# YYB-Sheet1.net
KiCad netlist of a schematic drawn in Altium Designer
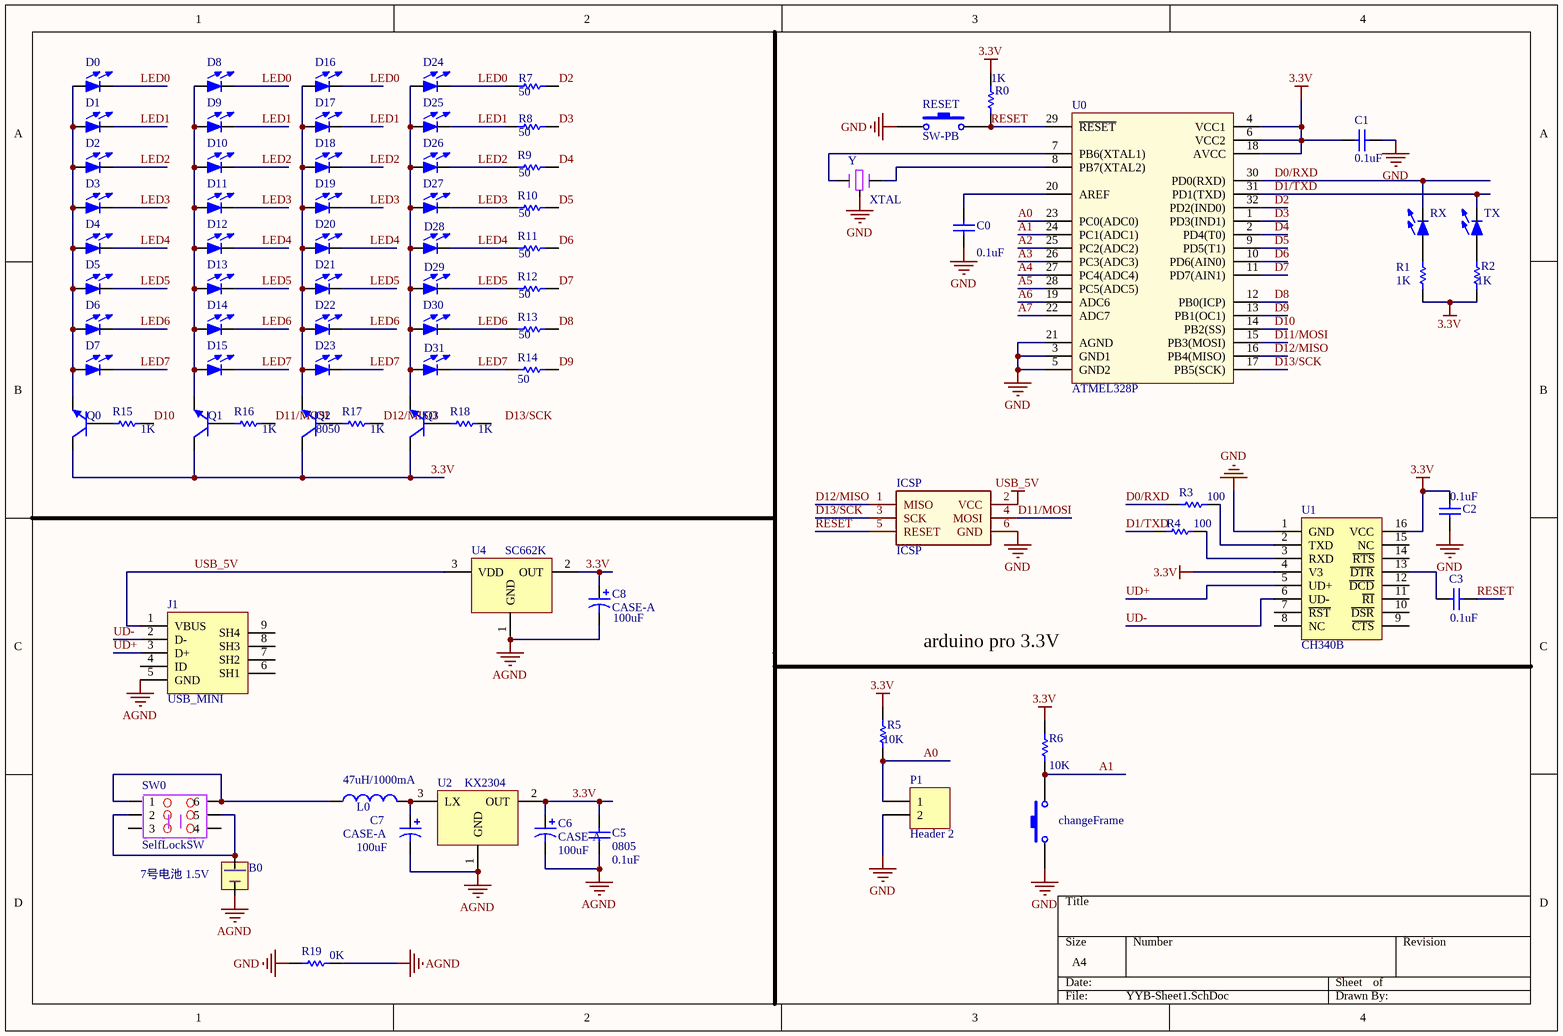
[diagram p0: YYB-Sheet1.SchDoc]

(export (version "E")
  (design (tool "Eeschema 10.0.6"))
  (components
    (comp (ref "B0") (value "7号电池 1.5V") (footprint "BAT") (libsource (lib "aistlab") (part "Battery")))
    (comp (ref "C0")
      (value "0.1uF")
      (footprint "6-0805_N")
      (description "Capacitor")
      (fields (field (name "PUBLISHER") "Altium Limited"))
      (libsource (lib "Miscellaneous Devices") (part "Cap"))
    )
    (comp (ref "C1")
      (value "0.1uF")
      (footprint "6-0805_N")
      (description "Capacitor")
      (fields (field (name "Comment") "Cap") (field (name "PUBLISHER") "Altium Limited"))
      (libsource (lib "Miscellaneous Devices") (part "Cap"))
    )
    (comp (ref "C2")
      (value "0.1uF")
      (footprint "6-0805_N")
      (description "Capacitor")
      (fields (field (name "Comment") "Cap") (field (name "PUBLISHER") "Altium Limited"))
      (libsource (lib "Miscellaneous Devices") (part "Cap"))
    )
    (comp (ref "C3")
      (value "0.1uF")
      (footprint "6-0805_N")
      (description "Capacitor")
      (fields (field (name "Comment") "Cap") (field (name "PUBLISHER") "Altium Limited"))
      (libsource (lib "Miscellaneous Devices") (part "Cap"))
    )
    (comp (ref "C5")
      (value "0805")
      (footprint "6-0805_N")
      (description "Capacitor")
      (fields (field (name "ALTIUM_VALUE") "0.1uF") (field (name "PUBLISHER") "Altium Limited"))
      (libsource (lib "Miscellaneous Devices") (part "Cap"))
    )
    (comp (ref "C6")
      (value "CASE-A")
      (footprint "CASE-A_3216")
      (description "Polarized Capacitor (Radial)")
      (fields (field (name "ALTIUM_VALUE") "100uF") (field (name "PUBLISHER") "Altium Limited"))
      (libsource (lib "Miscellaneous Devices") (part "Cap Pol1"))
    )
    (comp (ref "C7")
      (value "CASE-A")
      (footprint "CASE-A_3216")
      (description "Polarized Capacitor (Radial)")
      (fields (field (name "ALTIUM_VALUE") "100uF") (field (name "PUBLISHER") "Altium Limited"))
      (libsource (lib "Miscellaneous Devices") (part "Cap Pol1"))
    )
    (comp (ref "C8")
      (value "CASE-A")
      (footprint "CASE-A_3216")
      (description "Polarized Capacitor (Radial)")
      (fields (field (name "ALTIUM_VALUE") "100uF") (field (name "PUBLISHER") "Altium Limited"))
      (libsource (lib "Miscellaneous Devices") (part "Cap Pol1"))
    )
    (comp (ref "changeFrame")
      (value "SW-PB")
      (footprint "KEY_SODFL_2-Leads")
      (description "Switch")
      (fields (field (name "PUBLISHER") "Altium Limited"))
      (libsource (lib "Miscellaneous Devices") (part "SW-PB"))
    )
    (comp (ref "D0") (value "~") (footprint "LED_3528") (libsource (lib "aistlab") (part "LED")))
    (comp (ref "D1") (value "~") (footprint "LED_3528") (libsource (lib "aistlab") (part "LED")))
    (comp (ref "D2") (value "~") (footprint "LED_3528") (libsource (lib "aistlab") (part "LED")))
    (comp (ref "D3") (value "~") (footprint "LED_3528") (libsource (lib "aistlab") (part "LED")))
    (comp (ref "D4") (value "~") (footprint "LED_3528") (libsource (lib "aistlab") (part "LED")))
    (comp (ref "D5") (value "~") (footprint "LED_3528") (libsource (lib "aistlab") (part "LED")))
    (comp (ref "D6") (value "~") (footprint "LED_3528") (libsource (lib "aistlab") (part "LED")))
    (comp (ref "D7") (value "~") (footprint "LED_3528") (libsource (lib "aistlab") (part "LED")))
    (comp (ref "D8") (value "~") (footprint "LED_3528") (libsource (lib "aistlab") (part "LED")))
    (comp (ref "D9") (value "~") (footprint "LED_3528") (libsource (lib "aistlab") (part "LED")))
    (comp (ref "D10") (value "~") (footprint "LED_3528") (libsource (lib "aistlab") (part "LED")))
    (comp (ref "D11") (value "~") (footprint "LED_3528") (libsource (lib "aistlab") (part "LED")))
    (comp (ref "D12") (value "~") (footprint "LED_3528") (libsource (lib "aistlab") (part "LED")))
    (comp (ref "D13") (value "~") (footprint "LED_3528") (libsource (lib "aistlab") (part "LED")))
    (comp (ref "D14") (value "~") (footprint "LED_3528") (libsource (lib "aistlab") (part "LED")))
    (comp (ref "D15") (value "~") (footprint "LED_3528") (libsource (lib "aistlab") (part "LED")))
    (comp (ref "D16") (value "~") (footprint "LED_3528") (libsource (lib "aistlab") (part "LED")))
    (comp (ref "D17") (value "~") (footprint "LED_3528") (libsource (lib "aistlab") (part "LED")))
    (comp (ref "D18") (value "~") (footprint "LED_3528") (libsource (lib "aistlab") (part "LED")))
    (comp (ref "D19") (value "~") (footprint "LED_3528") (libsource (lib "aistlab") (part "LED")))
    (comp (ref "D20") (value "~") (footprint "LED_3528") (libsource (lib "aistlab") (part "LED")))
    (comp (ref "D21") (value "~") (footprint "LED_3528") (libsource (lib "aistlab") (part "LED")))
    (comp (ref "D22") (value "~") (footprint "LED_3528") (libsource (lib "aistlab") (part "LED")))
    (comp (ref "D23") (value "~") (footprint "LED_3528") (libsource (lib "aistlab") (part "LED")))
    (comp (ref "D24") (value "~") (footprint "LED_3528") (libsource (lib "aistlab") (part "LED")))
    (comp (ref "D25") (value "~") (footprint "LED_3528") (libsource (lib "aistlab") (part "LED")))
    (comp (ref "D26") (value "~") (footprint "LED_3528") (libsource (lib "aistlab") (part "LED")))
    (comp (ref "D27") (value "~") (footprint "LED_3528") (libsource (lib "aistlab") (part "LED")))
    (comp (ref "D28") (value "~") (footprint "LED_3528") (libsource (lib "aistlab") (part "LED")))
    (comp (ref "D29") (value "~") (footprint "LED_3528") (libsource (lib "aistlab") (part "LED")))
    (comp (ref "D30") (value "~") (footprint "LED_3528") (libsource (lib "aistlab") (part "LED")))
    (comp (ref "D31") (value "~") (footprint "LED_3528") (libsource (lib "aistlab") (part "LED")))
    (comp (ref "ICSP") (value "ICSP") (footprint "HDR2X3") (libsource (lib "aistlab") (part "ICSP")))
    (comp (ref "J1")
      (value "USB_MINI")
      (footprint "MICRO_USB")
      (libsource (lib "YYB-Schlib1") (part "USB_MINI"))
    )
    (comp (ref "L0")
      (value "47uH/1000mA")
      (footprint "0402-A")
      (description "Inductor")
      (fields (field (name "PUBLISHER") "Altium Limited"))
      (libsource (lib "Miscellaneous Devices") (part "Inductor"))
    )
    (comp (ref "P1")
      (value "Header 2")
      (footprint "HDR1X2")
      (description "Header, 2-Pin")
      (fields (field (name "PUBLISHER") "Altium Limited"))
      (libsource (lib "Miscellaneous Connectors") (part "Header 2"))
    )
    (comp (ref "Q0")
      (value "transistor")
      (footprint "SOT-23")
      (libsource (lib "aistlab") (part "transistor"))
    )
    (comp (ref "Q1")
      (value "transistor")
      (footprint "SOT-23")
      (libsource (lib "aistlab") (part "transistor"))
    )
    (comp (ref "Q2") (value "8050") (footprint "SOT-23") (libsource (lib "aistlab") (part "transistor")))
    (comp (ref "Q3")
      (value "transistor")
      (footprint "SOT-23")
      (libsource (lib "aistlab") (part "transistor"))
    )
    (comp (ref "R0")
      (value "1K")
      (footprint "6-0805_N")
      (description "Resistor")
      (fields (field (name "PUBLISHER") "Altium Limited"))
      (libsource (lib "Miscellaneous Devices") (part "Res1"))
    )
    (comp (ref "R1")
      (value "1K")
      (footprint "6-0805_N")
      (description "Resistor")
      (fields (field (name "Comment") "Res1") (field (name "PUBLISHER") "Altium Limited"))
      (libsource (lib "Miscellaneous Devices") (part "Res1"))
    )
    (comp (ref "R2")
      (value "1K")
      (footprint "6-0805_N")
      (description "Resistor")
      (fields (field (name "Comment") "Res1") (field (name "PUBLISHER") "Altium Limited"))
      (libsource (lib "Miscellaneous Devices") (part "Res1"))
    )
    (comp (ref "R3")
      (value "100")
      (footprint "6-0805_N")
      (description "Resistor")
      (fields (field (name "Comment") "Res1") (field (name "PUBLISHER") "Altium Limited"))
      (libsource (lib "Miscellaneous Devices") (part "Res1"))
    )
    (comp (ref "R4")
      (value "100")
      (footprint "6-0805_N")
      (description "Resistor")
      (fields (field (name "Comment") "Res1") (field (name "PUBLISHER") "Altium Limited"))
      (libsource (lib "Miscellaneous Devices") (part "Res1"))
    )
    (comp (ref "R5")
      (value "10K")
      (footprint "6-0805_N")
      (description "Resistor")
      (fields (field (name "Comment") "Res1") (field (name "PUBLISHER") "Altium Limited"))
      (libsource (lib "Miscellaneous Devices") (part "Res1"))
    )
    (comp (ref "R6")
      (value "10K")
      (footprint "6-0805_N")
      (description "Resistor")
      (fields (field (name "Comment") "Res1") (field (name "PUBLISHER") "Altium Limited"))
      (libsource (lib "Miscellaneous Devices") (part "Res1"))
    )
    (comp (ref "R7")
      (value "50")
      (footprint "6-0805_N")
      (description "Resistor")
      (fields (field (name "Comment") "Res1") (field (name "PUBLISHER") "Altium Limited"))
      (libsource (lib "Miscellaneous Devices") (part "Res1"))
    )
    (comp (ref "R8")
      (value "50")
      (footprint "6-0805_N")
      (description "Resistor")
      (fields (field (name "Comment") "Res1") (field (name "PUBLISHER") "Altium Limited"))
      (libsource (lib "Miscellaneous Devices") (part "Res1"))
    )
    (comp (ref "R9")
      (value "50")
      (footprint "6-0805_N")
      (description "Resistor")
      (fields (field (name "Comment") "Res1") (field (name "PUBLISHER") "Altium Limited"))
      (libsource (lib "Miscellaneous Devices") (part "Res1"))
    )
    (comp (ref "R10")
      (value "50")
      (footprint "6-0805_N")
      (description "Resistor")
      (fields (field (name "Comment") "Res1") (field (name "PUBLISHER") "Altium Limited"))
      (libsource (lib "Miscellaneous Devices") (part "Res1"))
    )
    (comp (ref "R11")
      (value "50")
      (footprint "6-0805_N")
      (description "Resistor")
      (fields (field (name "Comment") "Res1") (field (name "PUBLISHER") "Altium Limited"))
      (libsource (lib "Miscellaneous Devices") (part "Res1"))
    )
    (comp (ref "R12")
      (value "50")
      (footprint "6-0805_N")
      (description "Resistor")
      (fields (field (name "Comment") "Res1") (field (name "PUBLISHER") "Altium Limited"))
      (libsource (lib "Miscellaneous Devices") (part "Res1"))
    )
    (comp (ref "R13")
      (value "50")
      (footprint "6-0805_N")
      (description "Resistor")
      (fields (field (name "Comment") "Res1") (field (name "PUBLISHER") "Altium Limited"))
      (libsource (lib "Miscellaneous Devices") (part "Res1"))
    )
    (comp (ref "R14")
      (value "50")
      (description "Resistor")
      (fields (field (name "Comment") "Res1") (field (name "PUBLISHER") "Altium Limited"))
      (libsource (lib "Miscellaneous Devices") (part "Res1"))
    )
    (comp (ref "R15")
      (value "1K")
      (footprint "6-0805_N")
      (description "Resistor")
      (fields (field (name "Comment") "Res1") (field (name "PUBLISHER") "Altium Limited"))
      (libsource (lib "Miscellaneous Devices") (part "Res1"))
    )
    (comp (ref "R16")
      (value "1K")
      (footprint "6-0805_N")
      (description "Resistor")
      (fields (field (name "Comment") "Res1") (field (name "PUBLISHER") "Altium Limited"))
      (libsource (lib "Miscellaneous Devices") (part "Res1"))
    )
    (comp (ref "R17")
      (value "1K")
      (footprint "6-0805_N")
      (description "Resistor")
      (fields (field (name "Comment") "Res1") (field (name "PUBLISHER") "Altium Limited"))
      (libsource (lib "Miscellaneous Devices") (part "Res1"))
    )
    (comp (ref "R18")
      (value "1K")
      (footprint "6-0805_N")
      (description "Resistor")
      (fields (field (name "Comment") "Res1") (field (name "PUBLISHER") "Altium Limited"))
      (libsource (lib "Miscellaneous Devices") (part "Res1"))
    )
    (comp (ref "R19")
      (value "0K")
      (footprint "6-0805_N")
      (description "Resistor")
      (fields (field (name "Comment") "Res1") (field (name "PUBLISHER") "Altium Limited"))
      (libsource (lib "Miscellaneous Devices") (part "Res1"))
    )
    (comp (ref "RESET")
      (value "SW-PB")
      (footprint "KEY_SODFL_2-Leads")
      (description "Switch")
      (fields (field (name "PUBLISHER") "Altium Limited"))
      (libsource (lib "Miscellaneous Devices") (part "SW-PB"))
    )
    (comp (ref "RX") (value "~") (footprint "LED_0805") (libsource (lib "aistlab") (part "LED")))
    (comp (ref "SW0")
      (value "SelfLockSW")
      (footprint "KEY_ZS_8*8")
      (description "自锁开关")
      (libsource (lib "aistlab") (part "SelfLockSwitch"))
    )
    (comp (ref "TX") (value "~") (footprint "LED_0805") (libsource (lib "aistlab") (part "LED")))
    (comp (ref "U0")
      (value "ATMEL328P")
      (footprint "TQFP 32")
      (libsource (lib "aistlab") (part "ATMEL-328P"))
    )
    (comp (ref "U1")
      (value "CH340B")
      (footprint "SOP16")
      (description "usb to uart")
      (libsource (lib "aistlab") (part "CH340B"))
    )
    (comp (ref "U2") (value "KX2304") (footprint "SOT89N") (libsource (lib "aistlab") (part "KX2304")))
    (comp (ref "U4")
      (value "SC662K")
      (footprint "SOT-23")
      (description "3.3V 稳压芯片")
      (libsource (lib "aistlab") (part "SC662k-3.3V"))
    )
    (comp (ref "Y") (value "XTAL") (footprint "XTAL") (libsource (lib "aistlab") (part "XTAL")))
  )
  (nets
    (net (code "1") (name "/A0") (class "Default")
      (node (ref "P1") (pin "1") (pinfunction "1_1") (pintype "passive"))
      (node (ref "R5") (pin "1") (pinfunction "1_1") (pintype "passive"))
      (node (ref "U0") (pin "23") (pinfunction "PC0(ADC0)_23") (pintype "open_collector"))
    )
    (net (code "2") (name "/A1") (class "Default")
      (node (ref "R6") (pin "1") (pinfunction "1_1") (pintype "passive"))
      (node (ref "U0") (pin "24") (pinfunction "PC1(ADC1)_24") (pintype "open_collector"))
      (node (ref "changeFrame") (pin "2") (pinfunction "2_2") (pintype "passive"))
    )
    (net (code "3") (name "/A2") (class "Default")
      (node (ref "U0") (pin "25") (pinfunction "PC2(ADC2)_25") (pintype "open_collector"))
    )
    (net (code "4") (name "/A3") (class "Default")
      (node (ref "U0") (pin "26") (pinfunction "PC3(ADC3)_26") (pintype "open_collector"))
    )
    (net (code "5") (name "/A4") (class "Default")
      (node (ref "U0") (pin "27") (pinfunction "PC4(ADC4)_27") (pintype "open_collector"))
    )
    (net (code "6") (name "/A5") (class "Default")
      (node (ref "U0") (pin "28") (pinfunction "PC5(ADC5)_28") (pintype "open_collector"))
    )
    (net (code "7") (name "/A6") (class "Default")
      (node (ref "U0") (pin "19") (pinfunction "ADC6_19") (pintype "open_collector"))
    )
    (net (code "8") (name "/A7") (class "Default")
      (node (ref "U0") (pin "22") (pinfunction "ADC7_22") (pintype "open_collector"))
    )
    (net (code "9") (name "/D0{slash}RXD") (class "Default")
      (node (ref "R3") (pin "1") (pinfunction "1_1") (pintype "passive"))
      (node (ref "RX") (pin "2") (pinfunction "2_2") (pintype "passive"))
      (node (ref "U0") (pin "30") (pinfunction "PD0(RXD)_30") (pintype "open_collector"))
    )
    (net (code "10") (name "/D1{slash}TXD") (class "Default")
      (node (ref "R4") (pin "1") (pinfunction "1_1") (pintype "passive"))
      (node (ref "TX") (pin "2") (pinfunction "2_2") (pintype "passive"))
      (node (ref "U0") (pin "31") (pinfunction "PD1(TXD)_31") (pintype "open_collector"))
    )
    (net (code "11") (name "/D2") (class "Default")
      (node (ref "R7") (pin "2") (pinfunction "2_2") (pintype "passive"))
      (node (ref "U0") (pin "32") (pinfunction "PD2(IND0)_32") (pintype "open_collector"))
    )
    (net (code "12") (name "/D3") (class "Default")
      (node (ref "R8") (pin "2") (pinfunction "2_2") (pintype "passive"))
      (node (ref "U0") (pin "1") (pinfunction "PD3(IND1)_1") (pintype "open_collector"))
    )
    (net (code "13") (name "/D4") (class "Default")
      (node (ref "R9") (pin "2") (pinfunction "2_2") (pintype "passive"))
      (node (ref "U0") (pin "2") (pinfunction "PD4(T0)_2") (pintype "open_collector"))
    )
    (net (code "14") (name "/D5") (class "Default")
      (node (ref "R10") (pin "2") (pinfunction "2_2") (pintype "passive"))
      (node (ref "U0") (pin "9") (pinfunction "PD5(T1)_9") (pintype "open_collector"))
    )
    (net (code "15") (name "/D6") (class "Default")
      (node (ref "R11") (pin "2") (pinfunction "2_2") (pintype "passive"))
      (node (ref "U0") (pin "10") (pinfunction "PD6(AIN0)_10") (pintype "open_collector"))
    )
    (net (code "16") (name "/D7") (class "Default")
      (node (ref "R12") (pin "2") (pinfunction "2_2") (pintype "passive"))
      (node (ref "U0") (pin "11") (pinfunction "PD7(AIN1)_11") (pintype "open_collector"))
    )
    (net (code "17") (name "/D8") (class "Default")
      (node (ref "R13") (pin "2") (pinfunction "2_2") (pintype "passive"))
      (node (ref "U0") (pin "12") (pinfunction "PB0(ICP)_12") (pintype "open_collector"))
    )
    (net (code "18") (name "/D9") (class "Default")
      (node (ref "R14") (pin "2") (pinfunction "2_2") (pintype "passive"))
      (node (ref "U0") (pin "13") (pinfunction "PB1(OC1)_13") (pintype "open_collector"))
    )
    (net (code "19") (name "/D10") (class "Default")
      (node (ref "R15") (pin "2") (pinfunction "2_2") (pintype "passive"))
      (node (ref "U0") (pin "14") (pinfunction "PB2(SS)_14") (pintype "open_collector"))
    )
    (net (code "20") (name "/D11{slash}MOSI") (class "Default")
      (node (ref "ICSP") (pin "4") (pinfunction "MOSI_4") (pintype "open_collector"))
      (node (ref "R16") (pin "2") (pinfunction "2_2") (pintype "passive"))
      (node (ref "U0") (pin "15") (pinfunction "PB3(MOSI)_15") (pintype "open_collector"))
    )
    (net (code "21") (name "/D12{slash}MISO") (class "Default")
      (node (ref "ICSP") (pin "1") (pinfunction "MISO_1") (pintype "open_collector"))
      (node (ref "R17") (pin "2") (pinfunction "2_2") (pintype "passive"))
      (node (ref "U0") (pin "16") (pinfunction "PB4(MISO)_16") (pintype "open_collector"))
    )
    (net (code "22") (name "/D13{slash}SCK") (class "Default")
      (node (ref "ICSP") (pin "3") (pinfunction "SCK_3") (pintype "open_collector"))
      (node (ref "U0") (pin "17") (pinfunction "PB5(SCK)_17") (pintype "open_collector"))
    )
    (net (code "23") (name "/LED0") (class "Default")
      (node (ref "D0") (pin "2") (pinfunction "2_2") (pintype "passive"))
      (node (ref "D16") (pin "2") (pinfunction "2_2") (pintype "passive"))
      (node (ref "D24") (pin "2") (pinfunction "2_2") (pintype "passive"))
      (node (ref "D8") (pin "2") (pinfunction "2_2") (pintype "passive"))
      (node (ref "R7") (pin "1") (pinfunction "1_1") (pintype "passive"))
    )
    (net (code "24") (name "/LED1") (class "Default")
      (node (ref "D1") (pin "2") (pinfunction "2_2") (pintype "passive"))
      (node (ref "D17") (pin "2") (pinfunction "2_2") (pintype "passive"))
      (node (ref "D25") (pin "2") (pinfunction "2_2") (pintype "passive"))
      (node (ref "D9") (pin "2") (pinfunction "2_2") (pintype "passive"))
      (node (ref "R8") (pin "1") (pinfunction "1_1") (pintype "passive"))
    )
    (net (code "25") (name "/LED2") (class "Default")
      (node (ref "D10") (pin "2") (pinfunction "2_2") (pintype "passive"))
      (node (ref "D18") (pin "2") (pinfunction "2_2") (pintype "passive"))
      (node (ref "D2") (pin "2") (pinfunction "2_2") (pintype "passive"))
      (node (ref "D26") (pin "2") (pinfunction "2_2") (pintype "passive"))
      (node (ref "R9") (pin "1") (pinfunction "1_1") (pintype "passive"))
    )
    (net (code "26") (name "/LED3") (class "Default")
      (node (ref "D11") (pin "2") (pinfunction "2_2") (pintype "passive"))
      (node (ref "D19") (pin "2") (pinfunction "2_2") (pintype "passive"))
      (node (ref "D27") (pin "2") (pinfunction "2_2") (pintype "passive"))
      (node (ref "D3") (pin "2") (pinfunction "2_2") (pintype "passive"))
      (node (ref "R10") (pin "1") (pinfunction "1_1") (pintype "passive"))
    )
    (net (code "27") (name "/LED4") (class "Default")
      (node (ref "D12") (pin "2") (pinfunction "2_2") (pintype "passive"))
      (node (ref "D20") (pin "2") (pinfunction "2_2") (pintype "passive"))
      (node (ref "D28") (pin "2") (pinfunction "2_2") (pintype "passive"))
      (node (ref "D4") (pin "2") (pinfunction "2_2") (pintype "passive"))
      (node (ref "R11") (pin "1") (pinfunction "1_1") (pintype "passive"))
    )
    (net (code "28") (name "/LED5") (class "Default")
      (node (ref "D13") (pin "2") (pinfunction "2_2") (pintype "passive"))
      (node (ref "D21") (pin "2") (pinfunction "2_2") (pintype "passive"))
      (node (ref "D29") (pin "2") (pinfunction "2_2") (pintype "passive"))
      (node (ref "D5") (pin "2") (pinfunction "2_2") (pintype "passive"))
      (node (ref "R12") (pin "1") (pinfunction "1_1") (pintype "passive"))
    )
    (net (code "29") (name "/LED6") (class "Default")
      (node (ref "D14") (pin "2") (pinfunction "2_2") (pintype "passive"))
      (node (ref "D22") (pin "2") (pinfunction "2_2") (pintype "passive"))
      (node (ref "D30") (pin "2") (pinfunction "2_2") (pintype "passive"))
      (node (ref "D6") (pin "2") (pinfunction "2_2") (pintype "passive"))
      (node (ref "R13") (pin "1") (pinfunction "1_1") (pintype "passive"))
    )
    (net (code "30") (name "/LED7") (class "Default")
      (node (ref "D15") (pin "2") (pinfunction "2_2") (pintype "passive"))
      (node (ref "D23") (pin "2") (pinfunction "2_2") (pintype "passive"))
      (node (ref "D31") (pin "2") (pinfunction "2_2") (pintype "passive"))
      (node (ref "D7") (pin "2") (pinfunction "2_2") (pintype "passive"))
      (node (ref "R14") (pin "1") (pinfunction "1_1") (pintype "passive"))
    )
    (net (code "31") (name "/RESET") (class "Default")
      (node (ref "C3") (pin "2") (pinfunction "2_2") (pintype "passive"))
      (node (ref "ICSP") (pin "5") (pinfunction "RESET_5") (pintype "open_collector"))
      (node (ref "R0") (pin "2") (pinfunction "2_2") (pintype "passive"))
      (node (ref "RESET") (pin "2") (pinfunction "2_2") (pintype "passive"))
      (node (ref "U0") (pin "29") (pinfunction "~{RESET}_29") (pintype "open_collector"))
    )
    (net (code "32") (name "/UD+") (class "Default")
      (node (ref "J1") (pin "3") (pinfunction "D+_3") (pintype "passive"))
      (node (ref "U1") (pin "5") (pinfunction "UD+_5") (pintype "open_collector"))
    )
    (net (code "33") (name "/UD-") (class "Default")
      (node (ref "J1") (pin "2") (pinfunction "D-_2") (pintype "passive"))
      (node (ref "U1") (pin "6") (pinfunction "UD-_6") (pintype "open_collector"))
    )
    (net (code "34") (name "3.3V") (class "Default")
      (node (ref "C1") (pin "2") (pinfunction "2_2") (pintype "passive"))
      (node (ref "C2") (pin "2") (pinfunction "2_2") (pintype "passive"))
      (node (ref "C5") (pin "2") (pinfunction "2_2") (pintype "passive"))
      (node (ref "C6") (pin "1") (pinfunction "1_1") (pintype "passive"))
      (node (ref "C8") (pin "1") (pinfunction "1_1") (pintype "passive"))
      (node (ref "Q0") (pin "3") (pinfunction "C_3") (pintype "passive"))
      (node (ref "Q1") (pin "3") (pinfunction "C_3") (pintype "passive"))
      (node (ref "Q2") (pin "3") (pinfunction "C_3") (pintype "passive"))
      (node (ref "Q3") (pin "3") (pinfunction "C_3") (pintype "passive"))
      (node (ref "R0") (pin "1") (pinfunction "1_1") (pintype "passive"))
      (node (ref "R1") (pin "1") (pinfunction "1_1") (pintype "passive"))
      (node (ref "R2") (pin "1") (pinfunction "1_1") (pintype "passive"))
      (node (ref "R5") (pin "2") (pinfunction "2_2") (pintype "passive"))
      (node (ref "R6") (pin "2") (pinfunction "2_2") (pintype "passive"))
      (node (ref "U0") (pin "18") (pinfunction "AVCC_18") (pintype "power_in"))
      (node (ref "U0") (pin "4") (pinfunction "VCC1_4") (pintype "power_in"))
      (node (ref "U0") (pin "6") (pinfunction "VCC2_6") (pintype "power_in"))
      (node (ref "U1") (pin "16") (pinfunction "VCC_16") (pintype "power_in"))
      (node (ref "U1") (pin "4") (pinfunction "V3_4") (pintype "power_in"))
      (node (ref "U2") (pin "2") (pinfunction "OUT_2") (pintype "passive"))
      (node (ref "U4") (pin "2") (pinfunction "OUT_2") (pintype "passive"))
    )
    (net (code "35") (name "AGND") (class "Default")
      (node (ref "B0") (pin "2") (pinfunction "2_2") (pintype "passive"))
      (node (ref "C5") (pin "1") (pinfunction "1_1") (pintype "passive"))
      (node (ref "C6") (pin "2") (pinfunction "2_2") (pintype "passive"))
      (node (ref "C7") (pin "2") (pinfunction "2_2") (pintype "passive"))
      (node (ref "C8") (pin "2") (pinfunction "2_2") (pintype "passive"))
      (node (ref "J1") (pin "5") (pinfunction "GND_5") (pintype "passive"))
      (node (ref "R19") (pin "2") (pinfunction "2_2") (pintype "passive"))
      (node (ref "U2") (pin "1") (pinfunction "GND_1") (pintype "passive"))
      (node (ref "U4") (pin "1") (pinfunction "GND_1") (pintype "open_collector"))
    )
    (net (code "36") (name "GND") (class "Default")
      (node (ref "C0") (pin "1") (pinfunction "1_1") (pintype "passive"))
      (node (ref "C1") (pin "1") (pinfunction "1_1") (pintype "passive"))
      (node (ref "C2") (pin "1") (pinfunction "1_1") (pintype "passive"))
      (node (ref "ICSP") (pin "6") (pinfunction "GND_6") (pintype "open_collector"))
      (node (ref "P1") (pin "2") (pinfunction "2_2") (pintype "passive"))
      (node (ref "R19") (pin "1") (pinfunction "1_1") (pintype "passive"))
      (node (ref "RESET") (pin "1") (pinfunction "1_1") (pintype "passive"))
      (node (ref "U0") (pin "21") (pinfunction "AGND_21") (pintype "open_collector"))
      (node (ref "U0") (pin "3") (pinfunction "GND1_3") (pintype "open_collector"))
      (node (ref "U0") (pin "5") (pinfunction "GND2_5") (pintype "open_collector"))
      (node (ref "U1") (pin "1") (pinfunction "GND_1") (pintype "open_collector"))
      (node (ref "Y") (pin "2") (pinfunction "2_2") (pintype "passive"))
      (node (ref "changeFrame") (pin "1") (pinfunction "1_1") (pintype "passive"))
    )
    (net (code "37") (name "Net-(B0-+)") (class "Default")
      (node (ref "B0") (pin "1") (pinfunction "+_1") (pintype "passive"))
      (node (ref "SW0") (pin "2") (pinfunction "2_2") (pintype "passive"))
      (node (ref "SW0") (pin "5") (pinfunction "5_5") (pintype "passive"))
    )
    (net (code "38") (name "Net-(L0-Pad1)") (class "Default")
      (node (ref "L0") (pin "1") (pinfunction "1_1") (pintype "passive"))
      (node (ref "SW0") (pin "1") (pinfunction "1_1") (pintype "passive"))
      (node (ref "SW0") (pin "6") (pinfunction "6_6") (pintype "passive"))
    )
    (net (code "39") (name "Net-(Q0-B)") (class "Default")
      (node (ref "Q0") (pin "1") (pinfunction "B_1") (pintype "passive"))
      (node (ref "R15") (pin "1") (pinfunction "1_1") (pintype "passive"))
    )
    (net (code "40") (name "Net-(Q0-E)") (class "Default")
      (node (ref "D0") (pin "1") (pinfunction "1_1") (pintype "passive"))
      (node (ref "D1") (pin "1") (pinfunction "1_1") (pintype "passive"))
      (node (ref "D2") (pin "1") (pinfunction "1_1") (pintype "passive"))
      (node (ref "D3") (pin "1") (pinfunction "1_1") (pintype "passive"))
      (node (ref "D4") (pin "1") (pinfunction "1_1") (pintype "passive"))
      (node (ref "D5") (pin "1") (pinfunction "1_1") (pintype "passive"))
      (node (ref "D6") (pin "1") (pinfunction "1_1") (pintype "passive"))
      (node (ref "D7") (pin "1") (pinfunction "1_1") (pintype "passive"))
      (node (ref "Q0") (pin "2") (pinfunction "E_2") (pintype "passive"))
    )
    (net (code "41") (name "Net-(Q1-B)") (class "Default")
      (node (ref "Q1") (pin "1") (pinfunction "B_1") (pintype "passive"))
      (node (ref "R16") (pin "1") (pinfunction "1_1") (pintype "passive"))
    )
    (net (code "42") (name "Net-(Q1-E)") (class "Default")
      (node (ref "D10") (pin "1") (pinfunction "1_1") (pintype "passive"))
      (node (ref "D11") (pin "1") (pinfunction "1_1") (pintype "passive"))
      (node (ref "D12") (pin "1") (pinfunction "1_1") (pintype "passive"))
      (node (ref "D13") (pin "1") (pinfunction "1_1") (pintype "passive"))
      (node (ref "D14") (pin "1") (pinfunction "1_1") (pintype "passive"))
      (node (ref "D15") (pin "1") (pinfunction "1_1") (pintype "passive"))
      (node (ref "D8") (pin "1") (pinfunction "1_1") (pintype "passive"))
      (node (ref "D9") (pin "1") (pinfunction "1_1") (pintype "passive"))
      (node (ref "Q1") (pin "2") (pinfunction "E_2") (pintype "passive"))
    )
    (net (code "43") (name "Net-(Q2-B)") (class "Default")
      (node (ref "Q2") (pin "1") (pinfunction "B_1") (pintype "passive"))
      (node (ref "R17") (pin "1") (pinfunction "1_1") (pintype "passive"))
    )
    (net (code "44") (name "Net-(Q2-E)") (class "Default")
      (node (ref "D16") (pin "1") (pinfunction "1_1") (pintype "passive"))
      (node (ref "D17") (pin "1") (pinfunction "1_1") (pintype "passive"))
      (node (ref "D18") (pin "1") (pinfunction "1_1") (pintype "passive"))
      (node (ref "D19") (pin "1") (pinfunction "1_1") (pintype "passive"))
      (node (ref "D20") (pin "1") (pinfunction "1_1") (pintype "passive"))
      (node (ref "D21") (pin "1") (pinfunction "1_1") (pintype "passive"))
      (node (ref "D22") (pin "1") (pinfunction "1_1") (pintype "passive"))
      (node (ref "D23") (pin "1") (pinfunction "1_1") (pintype "passive"))
      (node (ref "Q2") (pin "2") (pinfunction "E_2") (pintype "passive"))
    )
    (net (code "45") (name "Net-(Q3-B)") (class "Default")
      (node (ref "Q3") (pin "1") (pinfunction "B_1") (pintype "passive"))
      (node (ref "R18") (pin "1") (pinfunction "1_1") (pintype "passive"))
    )
    (net (code "46") (name "Net-(Q3-E)") (class "Default")
      (node (ref "D24") (pin "1") (pinfunction "1_1") (pintype "passive"))
      (node (ref "D25") (pin "1") (pinfunction "1_1") (pintype "passive"))
      (node (ref "D26") (pin "1") (pinfunction "1_1") (pintype "passive"))
      (node (ref "D27") (pin "1") (pinfunction "1_1") (pintype "passive"))
      (node (ref "D28") (pin "1") (pinfunction "1_1") (pintype "passive"))
      (node (ref "D29") (pin "1") (pinfunction "1_1") (pintype "passive"))
      (node (ref "D30") (pin "1") (pinfunction "1_1") (pintype "passive"))
      (node (ref "D31") (pin "1") (pinfunction "1_1") (pintype "passive"))
      (node (ref "Q3") (pin "2") (pinfunction "E_2") (pintype "passive"))
    )
    (net (code "47") (name "Net-(R1-Pad2)") (class "Default")
      (node (ref "R1") (pin "2") (pinfunction "2_2") (pintype "passive"))
      (node (ref "RX") (pin "1") (pinfunction "1_1") (pintype "passive"))
    )
    (net (code "48") (name "Net-(R2-Pad2)") (class "Default")
      (node (ref "R2") (pin "2") (pinfunction "2_2") (pintype "passive"))
      (node (ref "TX") (pin "1") (pinfunction "1_1") (pintype "passive"))
    )
    (net (code "49") (name "Net-(U0-AREF)") (class "Default")
      (node (ref "C0") (pin "2") (pinfunction "2_2") (pintype "passive"))
      (node (ref "U0") (pin "20") (pinfunction "AREF_20") (pintype "open_collector"))
    )
    (net (code "50") (name "Net-(U0-PB6(XTAL1))") (class "Default")
      (node (ref "U0") (pin "7") (pinfunction "PB6(XTAL1)_7") (pintype "open_collector"))
      (node (ref "Y") (pin "1") (pinfunction "1_1") (pintype "passive"))
    )
    (net (code "51") (name "Net-(U0-PB7(XTAL2))") (class "Default")
      (node (ref "U0") (pin "8") (pinfunction "PB7(XTAL2)_8") (pintype "open_collector"))
      (node (ref "Y") (pin "3") (pinfunction "3_3") (pintype "passive"))
    )
    (net (code "52") (name "Net-(U1-RXD)") (class "Default")
      (node (ref "R4") (pin "2") (pinfunction "2_2") (pintype "passive"))
      (node (ref "U1") (pin "3") (pinfunction "RXD_3") (pintype "open_collector"))
    )
    (net (code "53") (name "Net-(U1-TXD)") (class "Default")
      (node (ref "R3") (pin "2") (pinfunction "2_2") (pintype "passive"))
      (node (ref "U1") (pin "2") (pinfunction "TXD_2") (pintype "open_collector"))
    )
    (net (code "54") (name "Net-(U1-~{DTR})") (class "Default")
      (node (ref "C3") (pin "1") (pinfunction "1_1") (pintype "passive"))
      (node (ref "U1") (pin "13") (pinfunction "~{DTR}_13") (pintype "open_collector"))
    )
    (net (code "55") (name "Net-(U2-LX)") (class "Default")
      (node (ref "C7") (pin "1") (pinfunction "1_1") (pintype "passive"))
      (node (ref "L0") (pin "2") (pinfunction "2_2") (pintype "passive"))
      (node (ref "U2") (pin "3") (pinfunction "LX_3") (pintype "passive"))
    )
    (net (code "56") (name "USB_5V") (class "Default")
      (node (ref "ICSP") (pin "2") (pinfunction "VCC_2") (pintype "passive"))
      (node (ref "J1") (pin "1") (pinfunction "VBUS_1") (pintype "passive"))
      (node (ref "U4") (pin "3") (pinfunction "VDD_3") (pintype "passive"))
    )
    (net (code "57") (name "unconnected-(J1-ID-Pad4)") (class "Default")
      (node (ref "J1") (pin "4") (pinfunction "ID_4") (pintype "passive"))
    )
    (net (code "58") (name "unconnected-(J1-SH1-Pad6)") (class "Default")
      (node (ref "J1") (pin "6") (pinfunction "SH1_6") (pintype "passive"))
    )
    (net (code "59") (name "unconnected-(J1-SH2-Pad7)") (class "Default")
      (node (ref "J1") (pin "7") (pinfunction "SH2_7") (pintype "passive"))
    )
    (net (code "60") (name "unconnected-(J1-SH3-Pad8)") (class "Default")
      (node (ref "J1") (pin "8") (pinfunction "SH3_8") (pintype "passive"))
    )
    (net (code "61") (name "unconnected-(J1-SH4-Pad9)") (class "Default")
      (node (ref "J1") (pin "9") (pinfunction "SH4_9") (pintype "passive"))
    )
    (net (code "62") (name "unconnected-(R18-Pad2)") (class "Default")
      (node (ref "R18") (pin "2") (pinfunction "2_2") (pintype "passive"))
    )
    (net (code "63") (name "unconnected-(SW0-Pad3)") (class "Default")
      (node (ref "SW0") (pin "3") (pinfunction "3_3") (pintype "passive"))
    )
    (net (code "64") (name "unconnected-(SW0-Pad4)") (class "Default")
      (node (ref "SW0") (pin "4") (pinfunction "4_4") (pintype "passive"))
    )
    (net (code "65") (name "unconnected-(U1-NC-Pad8)") (class "Default")
      (node (ref "U1") (pin "8") (pinfunction "NC_8") (pintype "passive"))
    )
    (net (code "66") (name "unconnected-(U1-NC-Pad15)") (class "Default")
      (node (ref "U1") (pin "15") (pinfunction "NC_15") (pintype "open_collector"))
    )
    (net (code "67") (name "unconnected-(U1-~{CTS}-Pad9)") (class "Default")
      (node (ref "U1") (pin "9") (pinfunction "~{CTS}_9") (pintype "open_collector"))
    )
    (net (code "68") (name "unconnected-(U1-~{DCD}-Pad12)") (class "Default")
      (node (ref "U1") (pin "12") (pinfunction "~{DCD}_12") (pintype "open_collector"))
    )
    (net (code "69") (name "unconnected-(U1-~{DSR}-Pad10)") (class "Default")
      (node (ref "U1") (pin "10") (pinfunction "~{DSR}_10") (pintype "open_collector"))
    )
    (net (code "70") (name "unconnected-(U1-~{RI}-Pad11)") (class "Default")
      (node (ref "U1") (pin "11") (pinfunction "~{RI}_11") (pintype "open_collector"))
    )
    (net (code "71") (name "unconnected-(U1-~{RST}-Pad7)") (class "Default")
      (node (ref "U1") (pin "7") (pinfunction "~{RST}_7") (pintype "open_collector"))
    )
    (net (code "72") (name "unconnected-(U1-~{RTS}-Pad14)") (class "Default")
      (node (ref "U1") (pin "14") (pinfunction "~{RTS}_14") (pintype "open_collector"))
    )
  )
)
